# 1_P1.net
KiCad netlist of a schematic drawn in Altium Designer
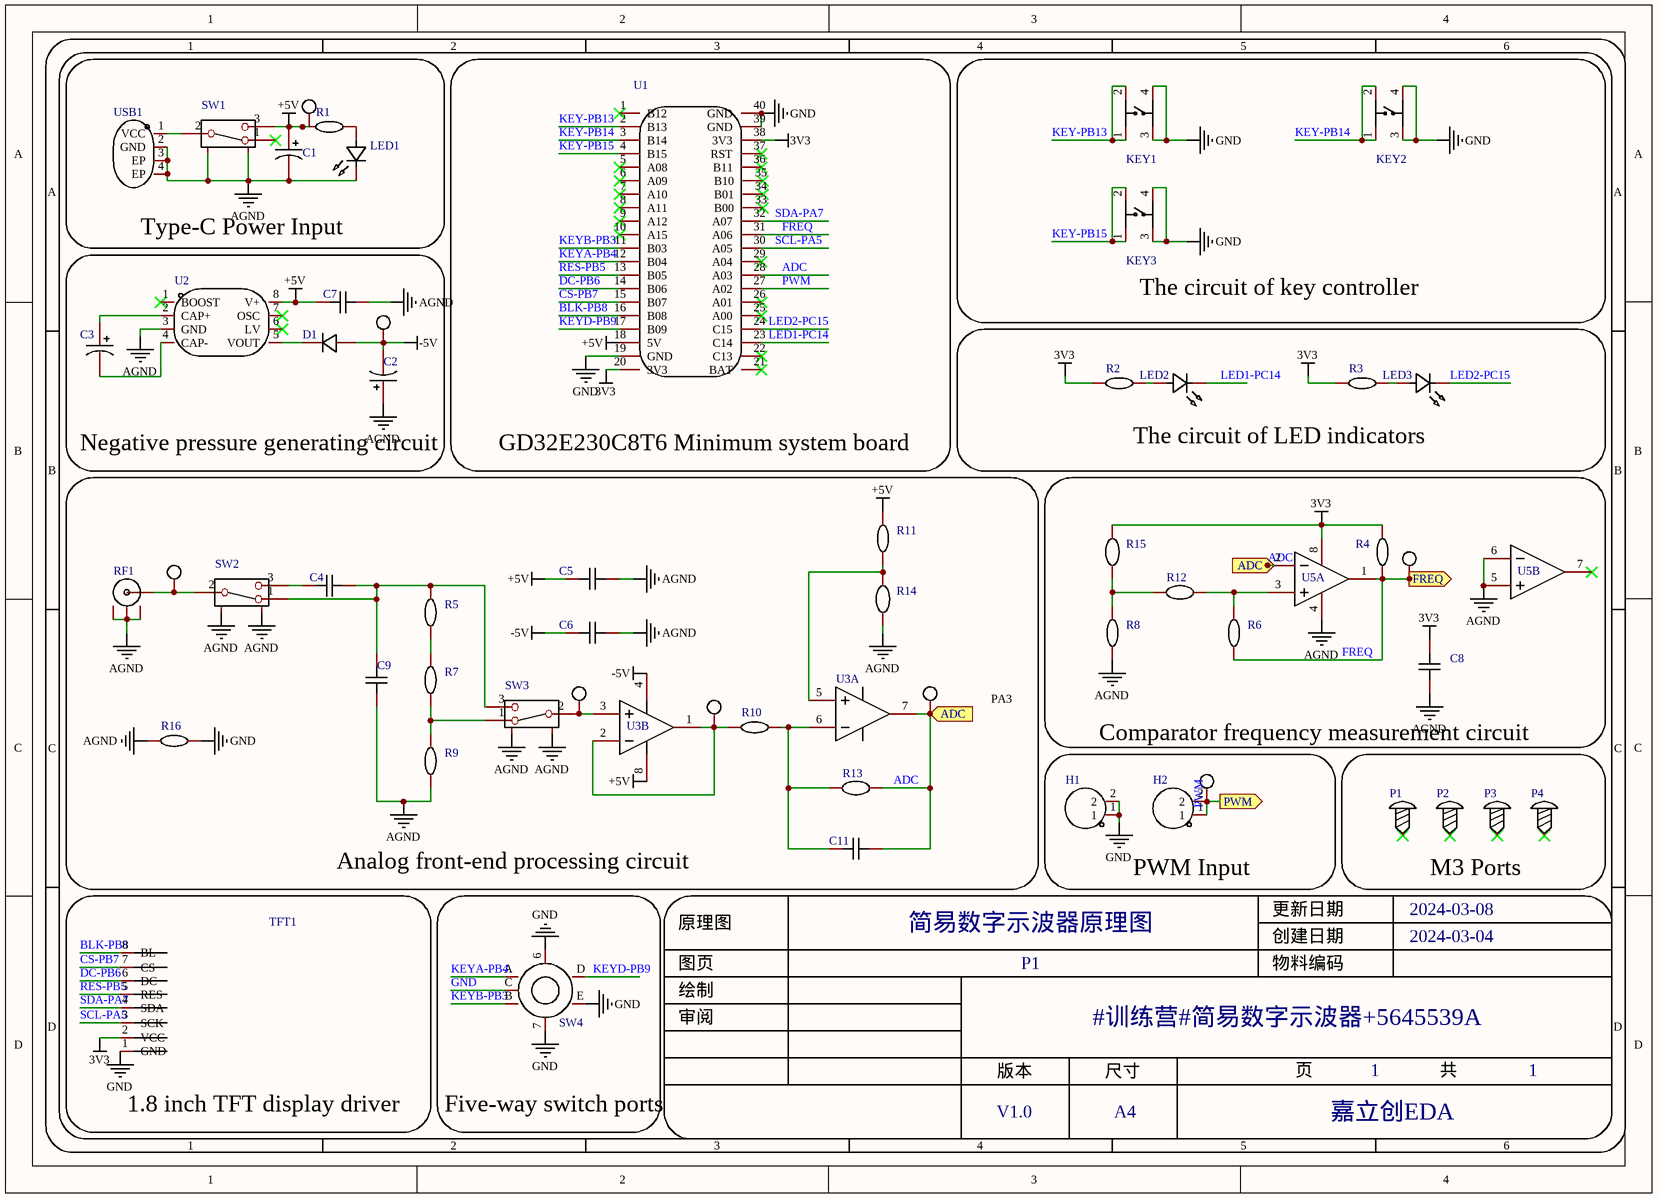
[diagram p0: 1_P1.schdoc]

(export (version "E")
  (design (tool "Eeschema 10.0.6"))
  (components
    (comp (ref "C1")
      (value "10uF")
      (footprint "CAP-TH_BD5.0-P2.00-D0.8-FD")
      (description "容值:10uF;精度:±20%;额定电压:50V;纹波电流:50mA@120Hz;等效串联电阻:-;")
      (fields
        (field (name "MANUFACTURER") "KNSCHA(科尼盛)")
        (field (name "MANUFACTURER PART") "01EC1809SHC10UF50V")
      )
      (libsource (lib "altium-import") (part "root_3_01EC1809SHC10UF50V_"))
    )
    (comp (ref "C2")
      (value "10uF")
      (footprint "CAP-TH_BD5.0-P2.00-D0.8-FD")
      (description "容值:10uF;精度:±20%;额定电压:50V;纹波电流:50mA@120Hz;等效串联电阻:-;")
      (fields
        (field (name "MANUFACTURER") "KNSCHA(科尼盛)")
        (field (name "MANUFACTURER PART") "01EC1809SHC10UF50V")
      )
      (libsource (lib "altium-import") (part "root_1_01EC1809SHC10UF50V_"))
    )
    (comp (ref "C3")
      (value "10uF")
      (footprint "CAP-TH_BD5.0-P2.00-D0.8-FD")
      (description "容值:10uF;精度:±20%;额定电压:50V;纹波电流:50mA@120Hz;等效串联电阻:-;")
      (fields
        (field (name "MANUFACTURER") "KNSCHA(科尼盛)")
        (field (name "MANUFACTURER PART") "01EC1809SHC10UF50V")
      )
      (libsource (lib "altium-import") (part "root_3_01EC1809SHC10UF50V_"))
    )
    (comp (ref "C4")
      (value "100nF")
      (footprint "CAP-TH_L4.2-W3.8-P2.54-D0.5")
      (description "容值:100nF;精度:±10%;额定电压:50V;温度系数:X7R;")
      (fields (field (name "MANUFACTURER") "FH(风华)") (field (name "MANUFACTURER PART") "CT4-0805B104K500F1"))
      (libsource (lib "altium-import") (part "root_0_CT4-0805B104K500F1_"))
    )
    (comp (ref "C5")
      (value "100nF")
      (footprint "CAP-TH_L4.2-W3.8-P2.54-D0.5")
      (description "容值:100nF;精度:±10%;额定电压:50V;温度系数:X7R;")
      (fields (field (name "MANUFACTURER") "FH(风华)") (field (name "MANUFACTURER PART") "CT4-0805B104K500F1"))
      (libsource (lib "altium-import") (part "root_0_CT4-0805B104K500F1_"))
    )
    (comp (ref "C6")
      (value "100nF")
      (footprint "CAP-TH_L4.2-W3.8-P2.54-D0.5")
      (description "容值:100nF;精度:±10%;额定电压:50V;温度系数:X7R;")
      (fields (field (name "MANUFACTURER") "FH(风华)") (field (name "MANUFACTURER PART") "CT4-0805B104K500F1"))
      (libsource (lib "altium-import") (part "root_0_CT4-0805B104K500F1_"))
    )
    (comp (ref "C7")
      (value "100nF")
      (footprint "CAP-TH_L4.2-W3.8-P2.54-D0.5")
      (description "容值:100nF;精度:±10%;额定电压:50V;温度系数:X7R;")
      (fields (field (name "MANUFACTURER") "FH(风华)") (field (name "MANUFACTURER PART") "CT4-0805B104K500F1"))
      (libsource (lib "altium-import") (part "root_0_CT4-0805B104K500F1_"))
    )
    (comp (ref "C8")
      (value "100nF")
      (footprint "CAP-TH_L4.2-W3.8-P2.54-D0.5")
      (description "容值:100nF;精度:±10%;额定电压:50V;温度系数:X7R;")
      (fields (field (name "MANUFACTURER") "FH(风华)") (field (name "MANUFACTURER PART") "CT4-0805B104K500F1"))
      (libsource (lib "altium-import") (part "root_1_CT4-0805B104K500F1_"))
    )
    (comp (ref "C9")
      (value "680pF")
      (footprint "CAP-TH_L5.5-W3.2-P5.00-D1.0")
      (description "容值:680pF;精度:±10%;额定电压:1kV;温度系数:Y5P;")
      (fields
        (field (name "MANUFACTURER") "Dersonic(德尔创)")
        (field (name "MANUFACTURER PART") "CC3A681KC1GEB45F30MF")
      )
      (libsource (lib "altium-import") (part "root_1_CC3A681KC1GEB45F30MF_"))
    )
    (comp (ref "C11")
      (value "10pF")
      (footprint "CAP-TH_L5.5-W2.5-P5.00-D1.0")
      (description "容值:10pF;精度:±10%;额定电压:1kV;温度系数:NP0;")
      (fields (field (name "MANUFACTURER") "STE(松田)") (field (name "MANUFACTURER PART") "N06A1B100KN0B0S0N0"))
      (libsource (lib "altium-import") (part "root_0_N06A1B100KN0B0S0N0_"))
    )
    (comp (ref "D1")
      (value "1N4148")
      (footprint "DO-35_BD2.0-L4.2-P8.20-D0.5-RD")
      (description "二极管配置:-;正向压降(Vf):1V@10mA;直流反向耐压(Vr):75V;平均整流电流(Io):150mA;功率:500mW;反向恢复时间(trr):4ns;")
      (fields (field (name "MANUFACTURER") "LGE(鲁光)"))
      (libsource (lib "altium-import") (part "root_0_1N4148_C402212_"))
    )
    (comp (ref "H1")
      (value "B-2100S02P-A110")
      (footprint "HDR-TH_2P-P2.54-V-M-1")
      (fields (field (name "MANUFACTURER") "Ckmtw(灿科盟)"))
      (libsource (lib "altium-import") (part "root_2_B-2100S02P-A110_"))
    )
    (comp (ref "H2")
      (value "B-2100S02P-A110")
      (footprint "HDR-TH_2P-P2.54-V-M-1")
      (fields (field (name "MANUFACTURER") "Ckmtw(灿科盟)"))
      (libsource (lib "altium-import") (part "root_2_B-2100S02P-A110_"))
    )
    (comp (ref "KEY1")
      (value "TC-6610-9-260G")
      (footprint "SW-TH_4P-L5.0-W5.0-P4.50-LS6.5")
      (fields (field (name "MANUFACTURER") "HCTL(华灿天禄)"))
      (libsource (lib "altium-import") (part "root_1_TC-6610-9-260G_"))
    )
    (comp (ref "KEY2")
      (value "TC-6610-9-260G")
      (footprint "SW-TH_4P-L5.0-W5.0-P4.50-LS6.5")
      (fields (field (name "MANUFACTURER") "HCTL(华灿天禄)"))
      (libsource (lib "altium-import") (part "root_1_TC-6610-9-260G_"))
    )
    (comp (ref "KEY3")
      (value "TC-6610-9-260G")
      (footprint "SW-TH_4P-L5.0-W5.0-P4.50-LS6.5")
      (fields (field (name "MANUFACTURER") "HCTL(华灿天禄)"))
      (libsource (lib "altium-import") (part "root_1_TC-6610-9-260G_"))
    )
    (comp (ref "LED1")
      (value "XL-302SURD")
      (footprint "LED-TH_BD3.8-P2.54-RD")
      (fields (field (name "MANUFACTURER") "XINGLIGHT(成兴光)"))
      (libsource (lib "altium-import") (part "root_1_XL-302SURD_"))
    )
    (comp (ref "LED2")
      (value "XL-304UGD")
      (footprint "LED-TH_BD3.8-P2.54-FD_GREEN")
      (fields (field (name "MANUFACTURER") "XINGLIGHT(成兴光)"))
      (libsource (lib "altium-import") (part "root_0_XL-304UGD_"))
    )
    (comp (ref "LED3")
      (value "XL-304UGD")
      (footprint "LED-TH_BD3.8-P2.54-FD_GREEN")
      (fields (field (name "MANUFACTURER") "XINGLIGHT(成兴光)"))
      (libsource (lib "altium-import") (part "root_0_XL-304UGD_"))
    )
    (comp (ref "P1")
      (value "M3螺丝")
      (footprint "M3螺丝")
      (libsource (lib "altium-import") (part "root_0_M3螺丝_"))
    )
    (comp (ref "P2")
      (value "M3螺丝")
      (footprint "M3螺丝")
      (libsource (lib "altium-import") (part "root_0_M3螺丝_"))
    )
    (comp (ref "P3")
      (value "M3螺丝")
      (footprint "M3螺丝")
      (libsource (lib "altium-import") (part "root_0_M3螺丝_"))
    )
    (comp (ref "P4")
      (value "M3螺丝")
      (footprint "M3螺丝")
      (libsource (lib "altium-import") (part "root_0_M3螺丝_"))
    )
    (comp (ref "R1")
      (value "1kΩ")
      (footprint "RES-TH_BD2.5-L6.5-P10.50-D0.6")
      (description "电阻类型:金属膜电阻;阻值:1kΩ;精度:±1%;功率:250mW;温度系数:±50ppm/℃;")
      (fields
        (field (name "MANUFACTURER") "UNI-ROYAL(厚声)")
        (field (name "MANUFACTURER PART") "MFR0W4F1001A50")
      )
      (libsource (lib "altium-import") (part "root_0_mirrored_MFR0W4F1001A50_"))
    )
    (comp (ref "R2")
      (value "1kΩ")
      (footprint "RES-TH_BD2.5-L6.5-P10.50-D0.6")
      (description "电阻类型:金属膜电阻;阻值:1kΩ;精度:±1%;功率:250mW;温度系数:±50ppm/℃;")
      (fields
        (field (name "MANUFACTURER") "UNI-ROYAL(厚声)")
        (field (name "MANUFACTURER PART") "MFR0W4F1001A50")
      )
      (libsource (lib "altium-import") (part "root_2_MFR0W4F1001A50_"))
    )
    (comp (ref "R3")
      (value "1kΩ")
      (footprint "RES-TH_BD2.5-L6.5-P10.50-D0.6")
      (description "电阻类型:金属膜电阻;阻值:1kΩ;精度:±1%;功率:250mW;温度系数:±50ppm/℃;")
      (fields
        (field (name "MANUFACTURER") "UNI-ROYAL(厚声)")
        (field (name "MANUFACTURER PART") "MFR0W4F1001A50")
      )
      (libsource (lib "altium-import") (part "root_2_MFR0W4F1001A50_"))
    )
    (comp (ref "R4")
      (value "1kΩ")
      (footprint "RES-TH_BD2.5-L6.5-P10.50-D0.6")
      (description "电阻类型:金属膜电阻;阻值:1kΩ;精度:±1%;功率:250mW;温度系数:±50ppm/℃;")
      (fields
        (field (name "MANUFACTURER") "UNI-ROYAL(厚声)")
        (field (name "MANUFACTURER PART") "MFR0W4F1001A50")
      )
      (libsource (lib "altium-import") (part "root_1_MFR0W4F1001A50_"))
    )
    (comp (ref "R5")
      (value "510kΩ")
      (footprint "RES-TH_BD2.3-L6.5-P10.50-D0.5")
      (description "电阻类型:金属膜电阻;阻值:510kΩ;精度:±1%;功率:250mW;温度系数:±100ppm/℃;")
      (fields
        (field (name "MANUFACTURER") "CCO(千志电子)")
        (field (name "MANUFACTURER PART") "MF1/4W-510KΩ±1% T")
      )
      (libsource (lib "altium-import") (part "root_1_MF1/4W-510KΩ±1% T_"))
    )
    (comp (ref "R6")
      (value "510kΩ")
      (footprint "RES-TH_BD2.3-L6.5-P10.50-D0.5")
      (description "电阻类型:金属膜电阻;阻值:510kΩ;精度:±1%;功率:250mW;温度系数:±100ppm/℃;")
      (fields
        (field (name "MANUFACTURER") "CCO(千志电子)")
        (field (name "MANUFACTURER PART") "MF1/4W-510KΩ±1% T")
      )
      (libsource (lib "altium-import") (part "root_1_MF1/4W-510KΩ±1% T_"))
    )
    (comp (ref "R7")
      (value "470kΩ")
      (footprint "RES-TH_BD2.2-L6.5-P10.50-D0.6")
      (description "电阻类型:金属膜电阻;阻值:470kΩ;精度:±1%;功率:250mW;温度系数:±50ppm/℃;")
      (fields
        (field (name "MANUFACTURER") "UNI-ROYAL(厚声)")
        (field (name "MANUFACTURER PART") "MFR0W4F4703A50")
      )
      (libsource (lib "altium-import") (part "root_1_MFR0W4F4703A50_"))
    )
    (comp (ref "R8")
      (value "20kΩ")
      (footprint "RES-TH_BD2.3-L6.5-P10.50-D0.5")
      (description "电阻类型:金属膜电阻;阻值:20kΩ;精度:±1%;功率:250mW;温度系数:±100ppm/℃;")
      (fields (field (name "MANUFACTURER") "CCO(千志电子)") (field (name "MANUFACTURER PART") "MF1/4W-20KΩ±1% T"))
      (libsource (lib "altium-import") (part "root_1_MF1/4W-20KΩ±1% T_"))
    )
    (comp (ref "R9")
      (value "20kΩ")
      (footprint "RES-TH_BD2.3-L6.5-P10.50-D0.5")
      (description "电阻类型:金属膜电阻;阻值:20kΩ;精度:±1%;功率:250mW;温度系数:±100ppm/℃;")
      (fields (field (name "MANUFACTURER") "CCO(千志电子)") (field (name "MANUFACTURER PART") "MF1/4W-20KΩ±1% T"))
      (libsource (lib "altium-import") (part "root_1_MF1/4W-20KΩ±1% T_"))
    )
    (comp (ref "R10")
      (value "20kΩ")
      (footprint "RES-TH_BD2.3-L6.5-P10.50-D0.5")
      (description "电阻类型:金属膜电阻;阻值:20kΩ;精度:±1%;功率:250mW;温度系数:±100ppm/℃;")
      (fields (field (name "MANUFACTURER") "CCO(千志电子)") (field (name "MANUFACTURER PART") "MF1/4W-20KΩ±1% T"))
      (libsource (lib "altium-import") (part "root_0_MF1/4W-20KΩ±1% T_"))
    )
    (comp (ref "R11")
      (value "20kΩ")
      (footprint "RES-TH_BD2.3-L6.5-P10.50-D0.5")
      (description "电阻类型:金属膜电阻;阻值:20kΩ;精度:±1%;功率:250mW;温度系数:±100ppm/℃;")
      (fields (field (name "MANUFACTURER") "CCO(千志电子)") (field (name "MANUFACTURER PART") "MF1/4W-20KΩ±1% T"))
      (libsource (lib "altium-import") (part "root_1_MF1/4W-20KΩ±1% T_"))
    )
    (comp (ref "R12")
      (value "10kΩ")
      (footprint "RES-TH_BD2.4-L6.3-P10.30-D0.6")
      (description "电阻类型:金属膜电阻;阻值:10kΩ;精度:±1%;功率:250mW;温度系数:±50ppm/℃;")
      (fields
        (field (name "MANUFACTURER") "Tyohm(幸亚电阻)")
        (field (name "MANUFACTURER PART") "RN1/4W10KFT/BA1")
      )
      (libsource (lib "altium-import") (part "root_0_RN1/4W10KFT/BA1_"))
    )
    (comp (ref "R13")
      (value "10kΩ")
      (footprint "RES-TH_BD2.4-L6.3-P10.30-D0.6")
      (description "电阻类型:金属膜电阻;阻值:10kΩ;精度:±1%;功率:250mW;温度系数:±50ppm/℃;")
      (fields
        (field (name "MANUFACTURER") "Tyohm(幸亚电阻)")
        (field (name "MANUFACTURER PART") "RN1/4W10KFT/BA1")
      )
      (libsource (lib "altium-import") (part "root_0_RN1/4W10KFT/BA1_"))
    )
    (comp (ref "R14")
      (value "10kΩ")
      (footprint "RES-TH_BD2.4-L6.3-P10.30-D0.6")
      (description "电阻类型:金属膜电阻;阻值:10kΩ;精度:±1%;功率:250mW;温度系数:±50ppm/℃;")
      (fields
        (field (name "MANUFACTURER") "Tyohm(幸亚电阻)")
        (field (name "MANUFACTURER PART") "RN1/4W10KFT/BA1")
      )
      (libsource (lib "altium-import") (part "root_1_RN1/4W10KFT/BA1_"))
    )
    (comp (ref "R15")
      (value "10kΩ")
      (footprint "RES-TH_BD2.4-L6.3-P10.30-D0.6")
      (description "电阻类型:金属膜电阻;阻值:10kΩ;精度:±1%;功率:250mW;温度系数:±50ppm/℃;")
      (fields
        (field (name "MANUFACTURER") "Tyohm(幸亚电阻)")
        (field (name "MANUFACTURER PART") "RN1/4W10KFT/BA1")
      )
      (libsource (lib "altium-import") (part "root_1_RN1/4W10KFT/BA1_"))
    )
    (comp (ref "R16")
      (value "0Ω")
      (footprint "RES-TH_BD2.3-L6.5-P10.50-D0.5")
      (description "电阻类型:金属膜电阻;阻值:20kΩ;精度:±1%;功率:250mW;温度系数:±100ppm/℃;")
      (fields (field (name "MANUFACTURER") "CCO(千志电子)") (field (name "MANUFACTURER PART") "MF1/4W-20KΩ±1% T"))
      (libsource (lib "altium-import") (part "root_2_MF1/4W-20KΩ±1% T_"))
    )
    (comp (ref "RF1")
      (value "KH-BNC50-3511")
      (footprint "ANT-TH_KH-BNC50-3511")
      (description "连接器类型:板端;接口类型:内孔;端口数量:1;接口直径:9.5mm;接口长度/高度:-;频率-最大值:3GHz;射频系列:BNC;阻抗:50Ω;样式:弯头;工作温度范围:-55℃~+155℃;")
      (fields (field (name "MANUFACTURER") "kinghelm(金航标)"))
      (libsource (lib "altium-import") (part "root_0_KH-BNC50-3511_"))
    )
    (comp (ref "SW1")
      (value "SK-12E12-G5")
      (footprint "SW-TH_SK-12E12-G5")
      (description "电路结构:单刀双掷;安装方式:侧插;额定电流(DC):-;额定电压(DC):-;额定电流(AC):-;额定电压(AC):-;机械寿命:5千次;")
      (fields (field (name "MANUFACTURER") "韩国韩荣"))
      (libsource (lib "altium-import") (part "root_0_SK-12E12-G5_"))
    )
    (comp (ref "SW2")
      (value "SK-12E12-G5")
      (footprint "SW-TH_SK-12E12-G5")
      (description "电路结构:单刀双掷;安装方式:侧插;额定电流(DC):-;额定电压(DC):-;额定电流(AC):-;额定电压(AC):-;机械寿命:5千次;")
      (fields (field (name "MANUFACTURER") "韩国韩荣"))
      (libsource (lib "altium-import") (part "root_0_SK-12E12-G5_"))
    )
    (comp (ref "SW3")
      (value "SK-12E12-G5")
      (footprint "SW-TH_SK-12E12-G5")
      (description "电路结构:单刀双掷;安装方式:侧插;额定电流(DC):-;额定电压(DC):-;额定电流(AC):-;额定电压(AC):-;机械寿命:5千次;")
      (fields (field (name "MANUFACTURER") "韩国韩荣"))
      (libsource (lib "altium-import") (part "root_0_mirrored_SK-12E12-G5_"))
    )
    (comp (ref "SW4")
      (value "EC11L1525G01")
      (footprint "SW-TH_ALPS_EC11L1525G01")
      (fields (field (name "MANUFACTURER") "ALPSALPINE(阿尔卑斯阿尔派)"))
      (libsource (lib "altium-import") (part "root_3_EC11L1525G01_"))
    )
    (comp (ref "TFT1")
      (value "1.8 TFT 128*RGB*160")
      (footprint "LCD-TH_8P-P2.54-L56.0-W34.0_1.8-TFT")
      (libsource (lib "altium-import") (part "root_0_1.8 TFT 128*RGB*160_"))
    )
    (comp (ref "U1")
      (value "LC-GD32E230C8T6")
      (footprint "DIP-40_L53.3-W22.9-P2.54-LS15.24")
      (description "4件套")
      (fields (field (name "MANUFACTURER") "立创开发板"))
      (libsource (lib "altium-import") (part "root_0_LC-GD32E230C8T6_"))
    )
    (comp (ref "U2")
      (value "XD7660")
      (footprint "DIP-8_L9.7-W6.4-P2.54-LS7.6-BL")
      (fields (field (name "MANUFACTURER") "XINLUDA(信路达)"))
      (libsource (lib "altium-import") (part "root_0_XD7660_"))
    )
    (comp (ref "U3")
      (value "TL072IP")
      (footprint "PDIP-8_L9.3-W6.4-P2.54-LS7.6-BL")
      (description "放大器数:双路;增益带宽积(GBP):5.25MHz;输入偏置电流(Ib):65pA;输入失调电压(Vos):3mV;压摆率(SR):13V/us;")
      (fields (field (name "MANUFACTURER") "TI(德州仪器)"))
      (libsource (lib "altium-import") (part "root_2_mirrored_TL072IP_"))
    )
    (comp (ref "U5")
      (value "LM393N")
      (footprint "DIP-8_L9.7-W6.4-P2.54-LS7.6-BL")
      (fields (field (name "MANUFACTURER") "HGSEMI(华冠)"))
      (libsource (lib "altium-import") (part "root_0_LM393N_"))
    )
    (comp (ref "U6")
      (value "TP1")
      (footprint "TESTPOINT-TH_BD3.2")
      (libsource (lib "altium-import") (part "root_1_TP-黄色测试点_"))
    )
    (comp (ref "U7")
      (value "TP2")
      (footprint "TESTPOINT-TH_BD3.2")
      (libsource (lib "altium-import") (part "root_1_TP-黄色测试点_"))
    )
    (comp (ref "U8")
      (value "TP3")
      (footprint "TESTPOINT-TH_BD3.2")
      (libsource (lib "altium-import") (part "root_1_TP-黄色测试点_"))
    )
    (comp (ref "U9")
      (value "TP5")
      (footprint "TESTPOINT-TH_BD3.2")
      (libsource (lib "altium-import") (part "root_1_TP-黄色测试点_"))
    )
    (comp (ref "U10")
      (value "TP4")
      (footprint "TESTPOINT-TH_BD3.2")
      (libsource (lib "altium-import") (part "root_1_TP-黄色测试点_"))
    )
    (comp (ref "U11")
      (value "TP6")
      (footprint "TESTPOINT-TH_BD3.2")
      (libsource (lib "altium-import") (part "root_1_TP-黄色测试点_"))
    )
    (comp (ref "U12")
      (value "TP7")
      (footprint "TESTPOINT-TH_BD3.2")
      (libsource (lib "altium-import") (part "root_1_TP-黄色测试点_"))
    )
    (comp (ref "U13")
      (value "TP8")
      (footprint "TESTPOINT-TH_BD3.2")
      (libsource (lib "altium-import") (part "root_1_TP-黄色测试点_"))
    )
    (comp (ref "USB1")
      (value "KH-TYPE-C-2P")
      (footprint "USB-SMD_KH-TYPE-C-2P")
      (description "连接器类型:Type-C;标准:-;公母:-;端口数量:-;触点数量:2P;安装方式:-;额定电流 - 电源:-;触头材质:-;触头镀层:-;工作温度范围:-;")
      (fields (field (name "MANUFACTURER") "kinghelm(金航标)"))
      (libsource (lib "altium-import") (part "root_0_mirrored_KH-TYPE-C-2P_"))
    )
  )
  (nets
    (net (code "1") (name "+5V") (class "Default")
      (node (ref "C1") (pin "1") (pinfunction "1_1") (pintype "passive"))
      (node (ref "C5") (pin "1") (pinfunction "1_1") (pintype "passive"))
      (node (ref "C7") (pin "1") (pinfunction "1_1") (pintype "passive"))
      (node (ref "R1") (pin "2") (pinfunction "2_2") (pintype "passive"))
      (node (ref "R11") (pin "2") (pinfunction "2_2") (pintype "passive"))
      (node (ref "SW1") (pin "3") (pinfunction "3_3") (pintype "passive"))
      (node (ref "U1") (pin "18") (pinfunction "5V_18") (pintype "passive"))
      (node (ref "U2") (pin "8") (pinfunction "V+_8") (pintype "passive"))
      (node (ref "U3") (pin "8") (pinfunction "VCC+_8") (pintype "passive"))
      (node (ref "U6") (pin "1") (pinfunction "1_1") (pintype "passive"))
    )
    (net (code "2") (name "-5V") (class "Default")
      (node (ref "C2") (pin "2") (pinfunction "2_2") (pintype "passive"))
      (node (ref "C6") (pin "1") (pinfunction "1_1") (pintype "passive"))
      (node (ref "D1") (pin "2") (pinfunction "A_2") (pintype "passive"))
      (node (ref "U3") (pin "4") (pinfunction "VCC-_4") (pintype "passive"))
      (node (ref "U7") (pin "1") (pinfunction "1_1") (pintype "passive"))
    )
    (net (code "3") (name "/ADC") (class "Default")
      (node (ref "C11") (pin "2") (pinfunction "2_2") (pintype "passive"))
      (node (ref "R13") (pin "2") (pinfunction "2_2") (pintype "passive"))
      (node (ref "U1") (pin "28") (pinfunction "A03_28") (pintype "passive"))
      (node (ref "U11") (pin "1") (pinfunction "1_1") (pintype "passive"))
      (node (ref "U3") (pin "7") (pinfunction "OUT2_7") (pintype "passive"))
      (node (ref "U5") (pin "2") (pinfunction "IN1-_2") (pintype "passive"))
    )
    (net (code "4") (name "/BLK-PB8") (class "Default")
      (node (ref "TFT1") (pin "8") (pinfunction "BL_8") (pintype "passive"))
      (node (ref "U1") (pin "16") (pinfunction "B08_16") (pintype "passive"))
    )
    (net (code "5") (name "/CS-PB7") (class "Default")
      (node (ref "TFT1") (pin "7") (pinfunction "CS_7") (pintype "passive"))
      (node (ref "U1") (pin "15") (pinfunction "B07_15") (pintype "passive"))
    )
    (net (code "6") (name "/DC-PB6") (class "Default")
      (node (ref "TFT1") (pin "6") (pinfunction "DC_6") (pintype "passive"))
      (node (ref "U1") (pin "14") (pinfunction "B06_14") (pintype "passive"))
    )
    (net (code "7") (name "/FREQ") (class "Default")
      (node (ref "R4") (pin "1") (pinfunction "1_1") (pintype "passive"))
      (node (ref "R6") (pin "1") (pinfunction "1_1") (pintype "passive"))
      (node (ref "U1") (pin "31") (pinfunction "A06_31") (pintype "passive"))
      (node (ref "U12") (pin "1") (pinfunction "1_1") (pintype "passive"))
      (node (ref "U5") (pin "1") (pinfunction "OUT1_1") (pintype "passive"))
    )
    (net (code "8") (name "/KEY-PB13") (class "Default")
      (node (ref "KEY1") (pin "1") (pinfunction "1_1") (pintype "passive"))
      (node (ref "KEY1") (pin "2") (pinfunction "2_2") (pintype "passive"))
      (node (ref "U1") (pin "2") (pinfunction "B13_2") (pintype "passive"))
    )
    (net (code "9") (name "/KEY-PB14") (class "Default")
      (node (ref "KEY2") (pin "1") (pinfunction "1_1") (pintype "passive"))
      (node (ref "KEY2") (pin "2") (pinfunction "2_2") (pintype "passive"))
      (node (ref "U1") (pin "3") (pinfunction "B14_3") (pintype "passive"))
    )
    (net (code "10") (name "/KEY-PB15") (class "Default")
      (node (ref "KEY3") (pin "1") (pinfunction "1_1") (pintype "passive"))
      (node (ref "KEY3") (pin "2") (pinfunction "2_2") (pintype "passive"))
      (node (ref "U1") (pin "4") (pinfunction "B15_4") (pintype "passive"))
    )
    (net (code "11") (name "/KEYA-PB4") (class "Default")
      (node (ref "SW4") (pin "A") (pinfunction "A_A") (pintype "passive"))
      (node (ref "U1") (pin "12") (pinfunction "B04_12") (pintype "passive"))
    )
    (net (code "12") (name "/KEYB-PB3") (class "Default")
      (node (ref "SW4") (pin "B") (pinfunction "B_B") (pintype "passive"))
      (node (ref "U1") (pin "11") (pinfunction "B03_11") (pintype "passive"))
    )
    (net (code "13") (name "/KEYD-PB9") (class "Default")
      (node (ref "SW4") (pin "D") (pinfunction "D_D") (pintype "passive"))
      (node (ref "U1") (pin "17") (pinfunction "B09_17") (pintype "passive"))
    )
    (net (code "14") (name "/LED1-PC14") (class "Default")
      (node (ref "LED2") (pin "2") (pinfunction "K_2") (pintype "passive"))
      (node (ref "U1") (pin "23") (pinfunction "C14_23") (pintype "passive"))
    )
    (net (code "15") (name "/LED2-PC15") (class "Default")
      (node (ref "LED3") (pin "2") (pinfunction "K_2") (pintype "passive"))
      (node (ref "U1") (pin "24") (pinfunction "C15_24") (pintype "passive"))
    )
    (net (code "16") (name "/PWM") (class "Default")
      (node (ref "H2") (pin "1") (pinfunction "1_1") (pintype "passive"))
      (node (ref "H2") (pin "2") (pinfunction "2_2") (pintype "passive"))
      (node (ref "U1") (pin "27") (pinfunction "A02_27") (pintype "passive"))
      (node (ref "U13") (pin "1") (pinfunction "1_1") (pintype "passive"))
    )
    (net (code "17") (name "/RES-PB5") (class "Default")
      (node (ref "TFT1") (pin "5") (pinfunction "RES_5") (pintype "passive"))
      (node (ref "U1") (pin "13") (pinfunction "B05_13") (pintype "passive"))
    )
    (net (code "18") (name "/SCL-PA5") (class "Default")
      (node (ref "TFT1") (pin "3") (pinfunction "SCK_3") (pintype "passive"))
      (node (ref "U1") (pin "30") (pinfunction "A05_30") (pintype "passive"))
    )
    (net (code "19") (name "/SDA-PA7") (class "Default")
      (node (ref "TFT1") (pin "4") (pinfunction "SDA_4") (pintype "passive"))
      (node (ref "U1") (pin "32") (pinfunction "A07_32") (pintype "passive"))
    )
    (net (code "20") (name "3V3") (class "Default")
      (node (ref "C8") (pin "2") (pinfunction "2_2") (pintype "passive"))
      (node (ref "R15") (pin "2") (pinfunction "2_2") (pintype "passive"))
      (node (ref "R2") (pin "2") (pinfunction "2_2") (pintype "passive"))
      (node (ref "R3") (pin "2") (pinfunction "2_2") (pintype "passive"))
      (node (ref "R4") (pin "2") (pinfunction "2_2") (pintype "passive"))
      (node (ref "TFT1") (pin "2") (pinfunction "VCC_2") (pintype "passive"))
      (node (ref "U1") (pin "20") (pinfunction "3V3_20") (pintype "passive"))
      (node (ref "U1") (pin "38") (pinfunction "3V3_38") (pintype "passive"))
      (node (ref "U5") (pin "8") (pinfunction "VCC+_8") (pintype "passive"))
    )
    (net (code "21") (name "AGND") (class "Default")
      (node (ref "C1") (pin "2") (pinfunction "2_2") (pintype "passive"))
      (node (ref "C2") (pin "1") (pinfunction "1_1") (pintype "passive"))
      (node (ref "C5") (pin "2") (pinfunction "2_2") (pintype "passive"))
      (node (ref "C6") (pin "2") (pinfunction "2_2") (pintype "passive"))
      (node (ref "C7") (pin "2") (pinfunction "2_2") (pintype "passive"))
      (node (ref "C8") (pin "1") (pinfunction "1_1") (pintype "passive"))
      (node (ref "C9") (pin "1") (pinfunction "1_1") (pintype "passive"))
      (node (ref "LED1") (pin "1") (pinfunction "K_1") (pintype "passive"))
      (node (ref "R14") (pin "1") (pinfunction "1_1") (pintype "passive"))
      (node (ref "R16") (pin "2") (pinfunction "2_2") (pintype "passive"))
      (node (ref "R8") (pin "1") (pinfunction "1_1") (pintype "passive"))
      (node (ref "R9") (pin "1") (pinfunction "1_1") (pintype "passive"))
      (node (ref "RF1") (pin "2") (pinfunction "2_2") (pintype "passive"))
      (node (ref "RF1") (pin "3") (pinfunction "3_3") (pintype "passive"))
      (node (ref "RF1") (pin "4") (pinfunction "4_4") (pintype "passive"))
      (node (ref "SW1") (pin "4") (pinfunction "4_4") (pintype "passive"))
      (node (ref "SW1") (pin "5") (pinfunction "5_5") (pintype "passive"))
      (node (ref "SW2") (pin "4") (pinfunction "4_4") (pintype "passive"))
      (node (ref "SW2") (pin "5") (pinfunction "5_5") (pintype "passive"))
      (node (ref "SW3") (pin "4") (pinfunction "4_4") (pintype "passive"))
      (node (ref "SW3") (pin "5") (pinfunction "5_5") (pintype "passive"))
      (node (ref "U2") (pin "3") (pinfunction "GND_3") (pintype "passive"))
      (node (ref "U5") (pin "4") (pinfunction "VCC-_4") (pintype "passive"))
      (node (ref "U5") (pin "5") (pinfunction "IN2+_5") (pintype "passive"))
      (node (ref "U5") (pin "6") (pinfunction "IN2-_6") (pintype "passive"))
      (node (ref "USB1") (pin "2") (pinfunction "GND_2") (pintype "passive"))
      (node (ref "USB1") (pin "3") (pinfunction "EP_3") (pintype "passive"))
      (node (ref "USB1") (pin "4") (pinfunction "EP_4") (pintype "passive"))
    )
    (net (code "22") (name "GND") (class "Default")
      (node (ref "H1") (pin "1") (pinfunction "1_1") (pintype "passive"))
      (node (ref "H1") (pin "2") (pinfunction "2_2") (pintype "passive"))
      (node (ref "KEY1") (pin "3") (pinfunction "3_3") (pintype "passive"))
      (node (ref "KEY1") (pin "4") (pinfunction "4_4") (pintype "passive"))
      (node (ref "KEY2") (pin "3") (pinfunction "3_3") (pintype "passive"))
      (node (ref "KEY2") (pin "4") (pinfunction "4_4") (pintype "passive"))
      (node (ref "KEY3") (pin "3") (pinfunction "3_3") (pintype "passive"))
      (node (ref "KEY3") (pin "4") (pinfunction "4_4") (pintype "passive"))
      (node (ref "R16") (pin "1") (pinfunction "1_1") (pintype "passive"))
      (node (ref "SW4") (pin "6") (pinfunction "EH_6") (pintype "passive"))
      (node (ref "SW4") (pin "7") (pinfunction "EH_7") (pintype "passive"))
      (node (ref "SW4") (pin "C") (pinfunction "C_C") (pintype "passive"))
      (node (ref "SW4") (pin "E") (pinfunction "E_E") (pintype "passive"))
      (node (ref "TFT1") (pin "1") (pinfunction "GND_1") (pintype "passive"))
      (node (ref "U1") (pin "19") (pinfunction "GND_19") (pintype "passive"))
      (node (ref "U1") (pin "39") (pinfunction "GND_39") (pintype "passive"))
      (node (ref "U1") (pin "40") (pinfunction "GND_40") (pintype "passive"))
    )
    (net (code "23") (name "Net-(C4-Pad1)") (class "Default")
      (node (ref "C4") (pin "1") (pinfunction "1_1") (pintype "passive"))
      (node (ref "SW2") (pin "3") (pinfunction "3_3") (pintype "passive"))
    )
    (net (code "24") (name "Net-(C4-Pad2)") (class "Default")
      (node (ref "C4") (pin "2") (pinfunction "2_2") (pintype "passive"))
      (node (ref "C9") (pin "2") (pinfunction "2_2") (pintype "passive"))
      (node (ref "R5") (pin "2") (pinfunction "2_2") (pintype "passive"))
      (node (ref "SW2") (pin "1") (pinfunction "1_1") (pintype "passive"))
      (node (ref "SW3") (pin "3") (pinfunction "3_3") (pintype "passive"))
    )
    (net (code "25") (name "Net-(D1-C)") (class "Default")
      (node (ref "D1") (pin "1") (pinfunction "C_1") (pintype "passive"))
      (node (ref "U2") (pin "5") (pinfunction "VOUT_5") (pintype "passive"))
    )
    (net (code "26") (name "Net-(LED1-A)") (class "Default")
      (node (ref "LED1") (pin "2") (pinfunction "A_2") (pintype "passive"))
      (node (ref "R1") (pin "1") (pinfunction "1_1") (pintype "passive"))
    )
    (net (code "27") (name "Net-(LED2-A)") (class "Default")
      (node (ref "LED2") (pin "1") (pinfunction "A_1") (pintype "passive"))
      (node (ref "R2") (pin "1") (pinfunction "1_1") (pintype "passive"))
    )
    (net (code "28") (name "Net-(LED3-A)") (class "Default")
      (node (ref "LED3") (pin "1") (pinfunction "A_1") (pintype "passive"))
      (node (ref "R3") (pin "1") (pinfunction "1_1") (pintype "passive"))
    )
    (net (code "29") (name "Net-(R5-Pad1)") (class "Default")
      (node (ref "R5") (pin "1") (pinfunction "1_1") (pintype "passive"))
      (node (ref "R7") (pin "2") (pinfunction "2_2") (pintype "passive"))
    )
    (net (code "30") (name "Net-(R7-Pad1)") (class "Default")
      (node (ref "R7") (pin "1") (pinfunction "1_1") (pintype "passive"))
      (node (ref "R9") (pin "2") (pinfunction "2_2") (pintype "passive"))
      (node (ref "SW3") (pin "1") (pinfunction "1_1") (pintype "passive"))
    )
    (net (code "31") (name "Net-(R12-Pad1)") (class "Default")
      (node (ref "R12") (pin "1") (pinfunction "1_1") (pintype "passive"))
      (node (ref "R15") (pin "1") (pinfunction "1_1") (pintype "passive"))
      (node (ref "R8") (pin "2") (pinfunction "2_2") (pintype "passive"))
    )
    (net (code "32") (name "Net-(RF1-OUT)") (class "Default")
      (node (ref "RF1") (pin "1") (pinfunction "OUT_1") (pintype "passive"))
      (node (ref "SW2") (pin "2") (pinfunction "2_2") (pintype "passive"))
      (node (ref "U10") (pin "1") (pinfunction "1_1") (pintype "passive"))
    )
    (net (code "33") (name "Net-(U2-CAP+)") (class "Default")
      (node (ref "C3") (pin "1") (pinfunction "1_1") (pintype "passive"))
      (node (ref "U2") (pin "2") (pinfunction "CAP+_2") (pintype "passive"))
    )
    (net (code "34") (name "Net-(U2-CAP-)") (class "Default")
      (node (ref "C3") (pin "2") (pinfunction "2_2") (pintype "passive"))
      (node (ref "U2") (pin "4") (pinfunction "CAP-_4") (pintype "passive"))
    )
    (net (code "35") (name "Net-(U3A-IN2+)") (class "Default")
      (node (ref "R11") (pin "1") (pinfunction "1_1") (pintype "passive"))
      (node (ref "R14") (pin "2") (pinfunction "2_2") (pintype "passive"))
      (node (ref "U3") (pin "5") (pinfunction "IN2+_5") (pintype "passive"))
    )
    (net (code "36") (name "Net-(U3A-IN2-)") (class "Default")
      (node (ref "C11") (pin "1") (pinfunction "1_1") (pintype "passive"))
      (node (ref "R10") (pin "2") (pinfunction "2_2") (pintype "passive"))
      (node (ref "R13") (pin "1") (pinfunction "1_1") (pintype "passive"))
      (node (ref "U3") (pin "6") (pinfunction "IN2-_6") (pintype "passive"))
    )
    (net (code "37") (name "Net-(U3B-IN1+)") (class "Default")
      (node (ref "SW3") (pin "2") (pinfunction "2_2") (pintype "passive"))
      (node (ref "U3") (pin "3") (pinfunction "IN1+_3") (pintype "passive"))
      (node (ref "U8") (pin "1") (pinfunction "1_1") (pintype "passive"))
    )
    (net (code "38") (name "Net-(U3B-IN1-)") (class "Default")
      (node (ref "R10") (pin "1") (pinfunction "1_1") (pintype "passive"))
      (node (ref "U3") (pin "1") (pinfunction "OUT1_1") (pintype "passive"))
      (node (ref "U3") (pin "2") (pinfunction "IN1-_2") (pintype "passive"))
      (node (ref "U9") (pin "1") (pinfunction "1_1") (pintype "passive"))
    )
    (net (code "39") (name "Net-(U5A-IN1+)") (class "Default")
      (node (ref "R12") (pin "2") (pinfunction "2_2") (pintype "passive"))
      (node (ref "R6") (pin "2") (pinfunction "2_2") (pintype "passive"))
      (node (ref "U5") (pin "3") (pinfunction "IN1+_3") (pintype "passive"))
    )
    (net (code "40") (name "Net-(USB1-VCC)") (class "Default")
      (node (ref "SW1") (pin "2") (pinfunction "2_2") (pintype "passive"))
      (node (ref "USB1") (pin "1") (pinfunction "VCC_1") (pintype "passive"))
    )
    (net (code "41") (name "unconnected-(P1-Pad1)") (class "Default")
      (node (ref "P1") (pin "1") (pinfunction "1_1") (pintype "passive+no_connect"))
    )
    (net (code "42") (name "unconnected-(P2-Pad1)") (class "Default")
      (node (ref "P2") (pin "1") (pinfunction "1_1") (pintype "passive+no_connect"))
    )
    (net (code "43") (name "unconnected-(P3-Pad1)") (class "Default")
      (node (ref "P3") (pin "1") (pinfunction "1_1") (pintype "passive+no_connect"))
    )
    (net (code "44") (name "unconnected-(P4-Pad1)") (class "Default")
      (node (ref "P4") (pin "1") (pinfunction "1_1") (pintype "passive+no_connect"))
    )
    (net (code "45") (name "unconnected-(SW1-Pad1)") (class "Default")
      (node (ref "SW1") (pin "1") (pinfunction "1_1") (pintype "passive+no_connect"))
    )
    (net (code "46") (name "unconnected-(U1-A00-Pad25)") (class "Default")
      (node (ref "U1") (pin "25") (pinfunction "A00_25") (pintype "passive+no_connect"))
    )
    (net (code "47") (name "unconnected-(U1-A01-Pad26)") (class "Default")
      (node (ref "U1") (pin "26") (pinfunction "A01_26") (pintype "passive+no_connect"))
    )
    (net (code "48") (name "unconnected-(U1-A04-Pad29)") (class "Default")
      (node (ref "U1") (pin "29") (pinfunction "A04_29") (pintype "passive+no_connect"))
    )
    (net (code "49") (name "unconnected-(U1-A08-Pad5)") (class "Default")
      (node (ref "U1") (pin "5") (pinfunction "A08_5") (pintype "passive+no_connect"))
    )
    (net (code "50") (name "unconnected-(U1-A09-Pad6)") (class "Default")
      (node (ref "U1") (pin "6") (pinfunction "A09_6") (pintype "passive+no_connect"))
    )
    (net (code "51") (name "unconnected-(U1-A10-Pad7)") (class "Default")
      (node (ref "U1") (pin "7") (pinfunction "A10_7") (pintype "passive+no_connect"))
    )
    (net (code "52") (name "unconnected-(U1-A11-Pad8)") (class "Default")
      (node (ref "U1") (pin "8") (pinfunction "A11_8") (pintype "passive+no_connect"))
    )
    (net (code "53") (name "unconnected-(U1-A12-Pad9)") (class "Default")
      (node (ref "U1") (pin "9") (pinfunction "A12_9") (pintype "passive+no_connect"))
    )
    (net (code "54") (name "unconnected-(U1-A15-Pad10)") (class "Default")
      (node (ref "U1") (pin "10") (pinfunction "A15_10") (pintype "passive+no_connect"))
    )
    (net (code "55") (name "unconnected-(U1-B00-Pad33)") (class "Default")
      (node (ref "U1") (pin "33") (pinfunction "B00_33") (pintype "passive+no_connect"))
    )
    (net (code "56") (name "unconnected-(U1-B01-Pad34)") (class "Default")
      (node (ref "U1") (pin "34") (pinfunction "B01_34") (pintype "passive+no_connect"))
    )
    (net (code "57") (name "unconnected-(U1-B10-Pad35)") (class "Default")
      (node (ref "U1") (pin "35") (pinfunction "B10_35") (pintype "passive+no_connect"))
    )
    (net (code "58") (name "unconnected-(U1-B11-Pad36)") (class "Default")
      (node (ref "U1") (pin "36") (pinfunction "B11_36") (pintype "passive+no_connect"))
    )
    (net (code "59") (name "unconnected-(U1-B12-Pad1)") (class "Default")
      (node (ref "U1") (pin "1") (pinfunction "B12_1") (pintype "passive+no_connect"))
    )
    (net (code "60") (name "unconnected-(U1-BAT-Pad21)") (class "Default")
      (node (ref "U1") (pin "21") (pinfunction "BAT_21") (pintype "passive+no_connect"))
    )
    (net (code "61") (name "unconnected-(U1-C13-Pad22)") (class "Default")
      (node (ref "U1") (pin "22") (pinfunction "C13_22") (pintype "passive+no_connect"))
    )
    (net (code "62") (name "unconnected-(U1-RST-Pad37)") (class "Default")
      (node (ref "U1") (pin "37") (pinfunction "RST_37") (pintype "passive+no_connect"))
    )
    (net (code "63") (name "unconnected-(U2-BOOST-Pad1)") (class "Default")
      (node (ref "U2") (pin "1") (pinfunction "BOOST_1") (pintype "passive+no_connect"))
    )
    (net (code "64") (name "unconnected-(U2-LV-Pad6)") (class "Default")
      (node (ref "U2") (pin "6") (pinfunction "LV_6") (pintype "passive+no_connect"))
    )
    (net (code "65") (name "unconnected-(U2-OSC-Pad7)") (class "Default")
      (node (ref "U2") (pin "7") (pinfunction "OSC_7") (pintype "passive+no_connect"))
    )
    (net (code "66") (name "unconnected-(U5B-OUT2-Pad7)") (class "Default")
      (node (ref "U5") (pin "7") (pinfunction "OUT2_7") (pintype "passive+no_connect"))
    )
  )
)
